# Connector-SDCard.net
KiCad netlist of a schematic drawn in Altium Designer
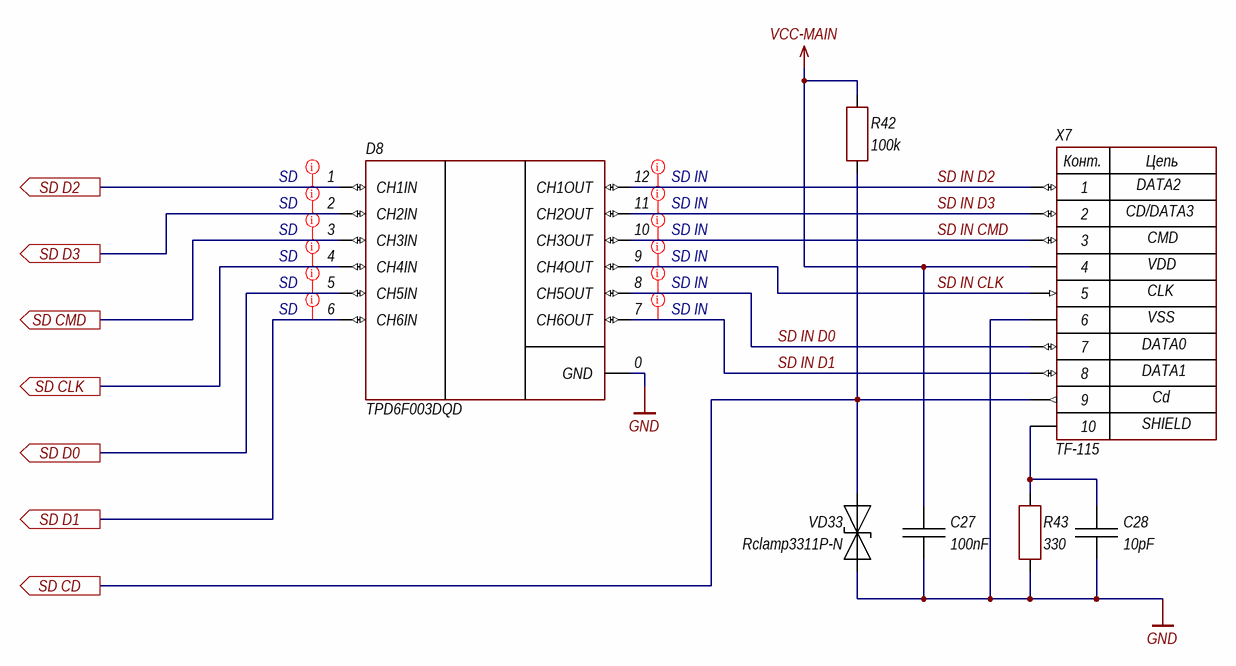
[diagram p0: Connector-SDCard.SchDoc]

(export (version "E")
  (design (tool "Eeschema 10.0.6"))
  (components
    (comp (ref "C27") (value "100nF") (footprint "CH0402C") (libsource (lib "Discrete") (part "Capacitor")))
    (comp (ref "C28") (value "10pF") (footprint "CH0402C") (libsource (lib "Discrete") (part "Capacitor")))
    (comp (ref "D8")
      (value "TPD6F003DQD")
      (footprint "12-WSON (2.5x1.35 mm)")
      (description "6-bit IO protection")
      (fields (field (name "MANUFACTURER") "Texas Instruments"))
      (libsource (lib "Analog") (part "TPD6F003"))
    )
    (comp (ref "R42") (value "100k") (footprint "CH0402R") (libsource (lib "Discrete") (part "Resistor")))
    (comp (ref "R43") (value "330") (footprint "CH0402R") (libsource (lib "Discrete") (part "Resistor")))
    (comp (ref "VD33")
      (value "Rclamp3311P-N")
      (footprint "DFN1006-2")
      (fields (field (name "MANUFACTURER") "BORN"))
      (libsource (lib "Diods") (part "TVS-diod"))
    )
    (comp (ref "X7")
      (value "TF-115")
      (footprint "CON: MicroSD 14x15mm")
      (description "µSD connector")
      (fields (field (name "MANUFACTURER") "XUNPU"))
      (libsource (lib "Connectors") (part "MicroSD"))
    )
  )
  (nets
    (net (code "1") (name "/SD CD") (class "Default")
      (node (ref "R42") (pin "1") (pinfunction "1_1") (pintype "passive"))
      (node (ref "VD33") (pin "2") (pinfunction "C_2") (pintype "passive"))
      (node (ref "X7") (pin "9") (pinfunction "9_9") (pintype "output"))
    )
    (net (code "2") (name "/SD CLK") (class "Default")
      (node (ref "D8") (pin "4") (pinfunction "CH4IN_4") (pintype "bidirectional"))
    )
    (net (code "3") (name "/SD CMD") (class "Default")
      (node (ref "D8") (pin "3") (pinfunction "CH3IN_3") (pintype "bidirectional"))
    )
    (net (code "4") (name "/SD D0") (class "Default")
      (node (ref "D8") (pin "5") (pinfunction "CH5IN_5") (pintype "bidirectional"))
    )
    (net (code "5") (name "/SD D1") (class "Default")
      (node (ref "D8") (pin "6") (pinfunction "CH6IN_6") (pintype "bidirectional"))
    )
    (net (code "6") (name "/SD D2") (class "Default")
      (node (ref "D8") (pin "1") (pinfunction "CH1IN_1") (pintype "bidirectional"))
    )
    (net (code "7") (name "/SD D3") (class "Default")
      (node (ref "D8") (pin "2") (pinfunction "CH2IN_2") (pintype "bidirectional"))
    )
    (net (code "8") (name "/SD IN CLK") (class "Default")
      (node (ref "D8") (pin "9") (pinfunction "CH4OUT_9") (pintype "bidirectional"))
      (node (ref "X7") (pin "5") (pinfunction "5_5") (pintype "input"))
    )
    (net (code "9") (name "/SD IN CMD") (class "Default")
      (node (ref "D8") (pin "10") (pinfunction "CH3OUT_10") (pintype "bidirectional"))
      (node (ref "X7") (pin "3") (pinfunction "3_3") (pintype "bidirectional"))
    )
    (net (code "10") (name "/SD IN D0") (class "Default")
      (node (ref "D8") (pin "8") (pinfunction "CH5OUT_8") (pintype "bidirectional"))
      (node (ref "X7") (pin "7") (pinfunction "7_7") (pintype "bidirectional"))
    )
    (net (code "11") (name "/SD IN D1") (class "Default")
      (node (ref "D8") (pin "7") (pinfunction "CH6OUT_7") (pintype "bidirectional"))
      (node (ref "X7") (pin "8") (pinfunction "8_8") (pintype "bidirectional"))
    )
    (net (code "12") (name "/SD IN D2") (class "Default")
      (node (ref "D8") (pin "12") (pinfunction "CH1OUT_12") (pintype "bidirectional"))
      (node (ref "X7") (pin "1") (pinfunction "1_1") (pintype "bidirectional"))
    )
    (net (code "13") (name "/SD IN D3") (class "Default")
      (node (ref "D8") (pin "11") (pinfunction "CH2OUT_11") (pintype "bidirectional"))
      (node (ref "X7") (pin "2") (pinfunction "2_2") (pintype "bidirectional"))
    )
    (net (code "14") (name "GND") (class "Default")
      (node (ref "C27") (pin "1") (pinfunction "1_1") (pintype "passive"))
      (node (ref "C28") (pin "1") (pinfunction "1_1") (pintype "passive"))
      (node (ref "D8") (pin "0") (pinfunction "GND_0") (pintype "power_in"))
      (node (ref "R43") (pin "1") (pinfunction "1_1") (pintype "passive"))
      (node (ref "VD33") (pin "1") (pinfunction "A_1") (pintype "passive"))
      (node (ref "X7") (pin "6") (pinfunction "6_6") (pintype "power_in"))
    )
    (net (code "15") (name "Net-(C28-Pad2)") (class "Default")
      (node (ref "C28") (pin "2") (pinfunction "2_2") (pintype "passive"))
      (node (ref "R43") (pin "2") (pinfunction "2_2") (pintype "passive"))
      (node (ref "X7") (pin "10") (pinfunction "10_10") (pintype "passive"))
    )
    (net (code "16") (name "VCC-MAIN") (class "Default")
      (node (ref "C27") (pin "2") (pinfunction "2_2") (pintype "passive"))
      (node (ref "R42") (pin "2") (pinfunction "2_2") (pintype "passive"))
      (node (ref "X7") (pin "4") (pinfunction "4_4") (pintype "power_in"))
    )
  )
)
